# BluJoy-2_1.net
KiCad netlist of a schematic drawn in EAGLE
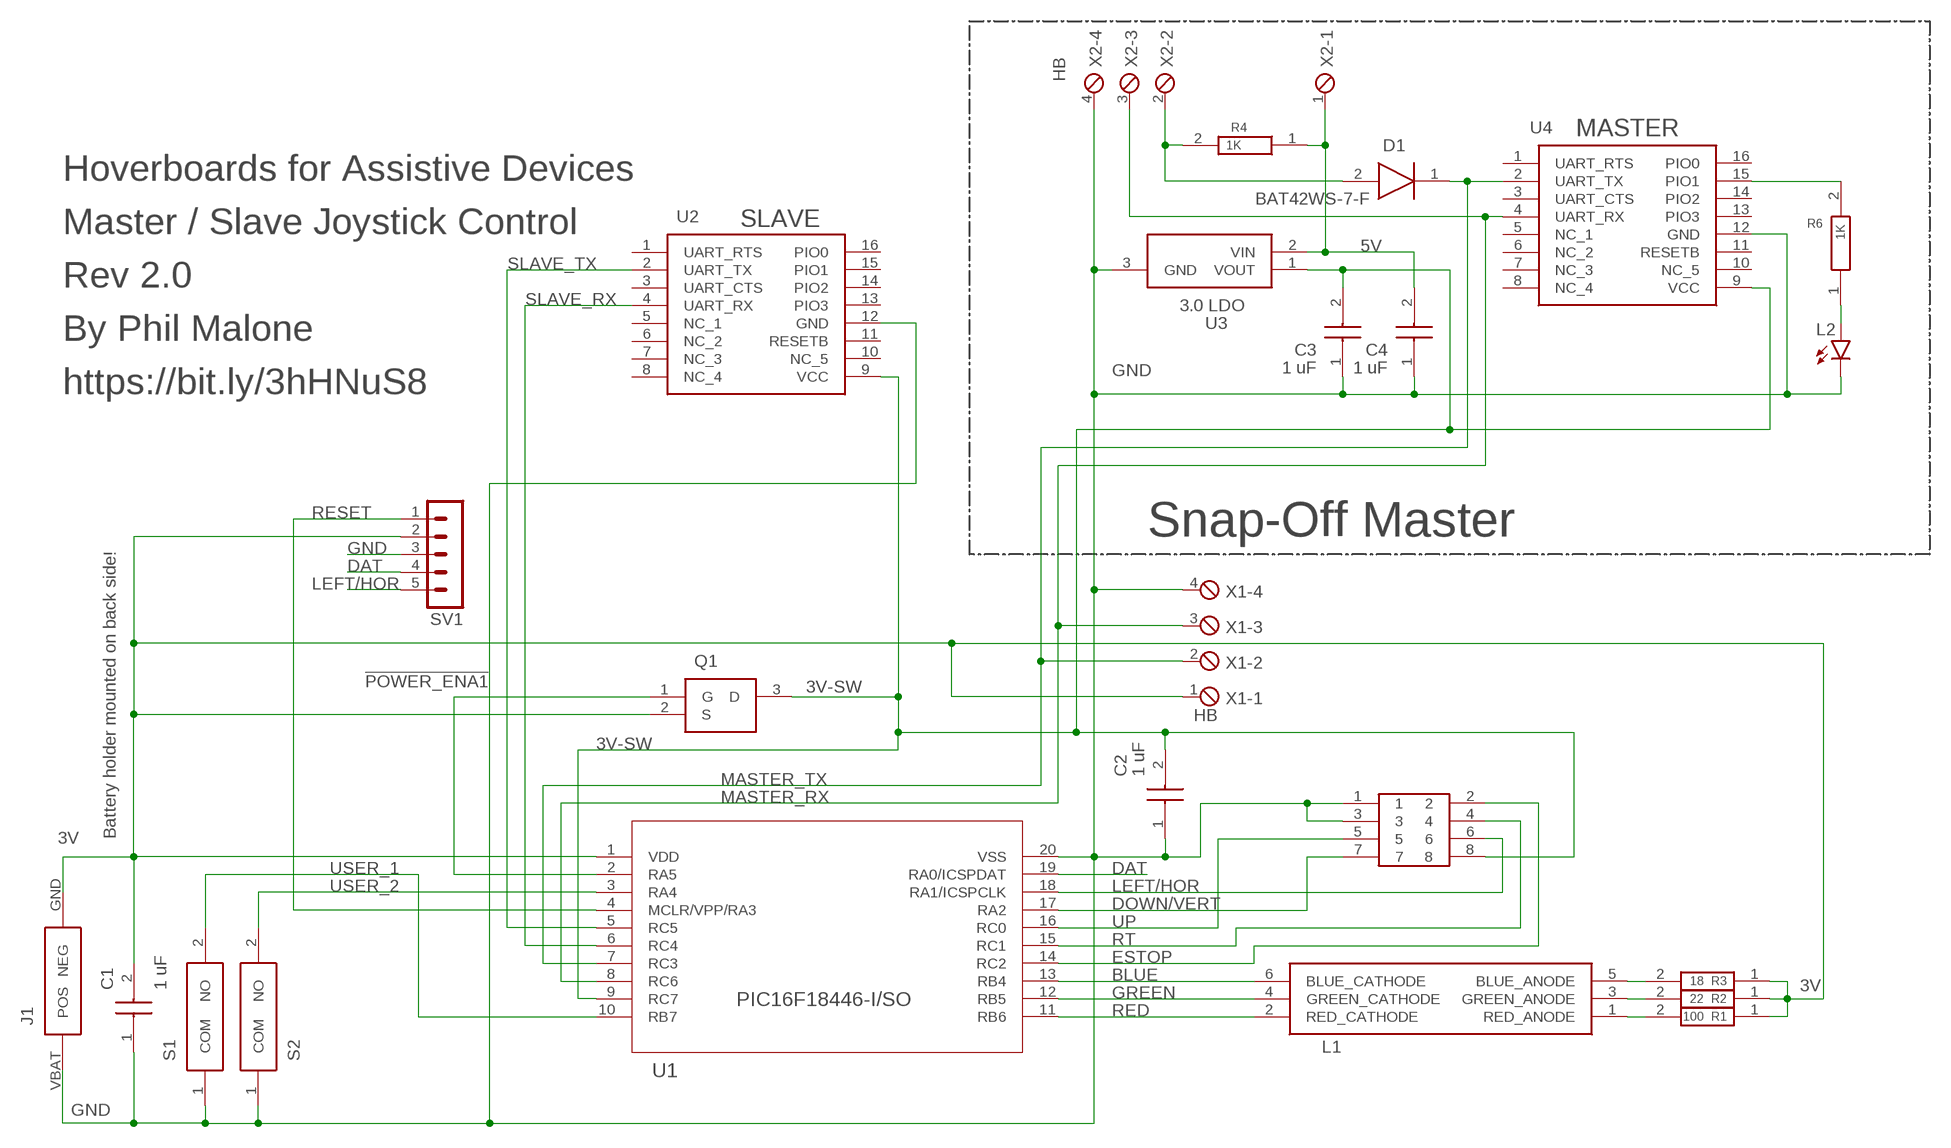
[diagram p0: schematic, sheet 1]

(export (version "E")
  (design (tool "Eeschema 10.0.6"))
  (components
    (comp (ref "C1")
      (value "1 uF")
      (footprint "eagle-import:CAPC1608X90N")
      (fields
        (field (name "MANUFACTURER_PART_NUMBER") "CC0603KRX7R7BB104")
        (field (name "MOUSER_PART_NUMBER") "603-CC603KRX7R7BB104")
        (field (name "RS_PART_NUMBER") "6698763")
      )
      (libsource (lib "eagle-import") (part "CC0603KRX7R7BB104"))
    )
    (comp (ref "C2")
      (value "1 uF")
      (footprint "eagle-import:CAPC1608X90N")
      (fields
        (field (name "MANUFACTURER_PART_NUMBER") "CC0603KRX7R7BB104")
        (field (name "MOUSER_PART_NUMBER") "603-CC603KRX7R7BB104")
        (field (name "RS_PART_NUMBER") "6698763")
      )
      (libsource (lib "eagle-import") (part "CC0603KRX7R7BB104"))
    )
    (comp (ref "C3")
      (value "1 uF")
      (footprint "eagle-import:CAPC1608X90N")
      (fields
        (field (name "MANUFACTURER_PART_NUMBER") "CC0603KRX7R7BB104")
        (field (name "MOUSER_PART_NUMBER") "603-CC603KRX7R7BB104")
        (field (name "RS_PART_NUMBER") "6698763")
      )
      (libsource (lib "eagle-import") (part "CC0603KRX7R7BB104"))
    )
    (comp (ref "C4")
      (value "1 uF")
      (footprint "eagle-import:CAPC1608X90N")
      (fields
        (field (name "MANUFACTURER_PART_NUMBER") "CC0603KRX7R7BB104")
        (field (name "MOUSER_PART_NUMBER") "603-CC603KRX7R7BB104")
        (field (name "RS_PART_NUMBER") "6698763")
      )
      (libsource (lib "eagle-import") (part "CC0603KRX7R7BB104"))
    )
    (comp (ref "D1")
      (value "BAT42WS-7-F")
      (footprint "eagle-import:SOD2513X120N")
      (fields (field (name "MOUSER_PART_NUMBER") "621-BAT42WS-F"))
      (libsource (lib "eagle-import") (part "BAT42WS-7-F"))
    )
    (comp (ref "J1")
      (value "2468")
      (footprint "eagle-import:2468")
      (fields (field (name "MOUSER_PART_NUMBER") "534-2468") (field (name "RS_PART_NUMBER") "2794965"))
      (libsource (lib "eagle-import") (part "2468"))
    )
    (comp (ref "J2")
      (value "PHOENIX3.5X8-B")
      (footprint "eagle-import:1751303")
      (libsource (lib "eagle-import") (part "PHOENIX3.5X8-B"))
    )
    (comp (ref "L1")
      (value "ASMB-TTF0-0A20B")
      (footprint "eagle-import:ASMBTTF00A20B")
      (fields (field (name "MOUSER_PART_NUMBER") "630-ASMB-TTF0-0A20B"))
      (libsource (lib "eagle-import") (part "ASMB-TTF0-0A20B"))
    )
    (comp (ref "L2")
      (value "LEDCHIP-LED0603")
      (footprint "eagle-import:CHIP-LED0603")
      (libsource (lib "eagle-import") (part "LEDCHIP-LED0603"))
    )
    (comp (ref "Q1")
      (value "P-FET")
      (footprint "eagle-import:SOT96P237X111-3N")
      (fields
        (field (name "ARROW_PART_NUMBER") "NTR4171PT1G")
        (field (name "MOUSER_PART_NUMBER") "863-NTR4171PT1G")
      )
      (libsource (lib "eagle-import") (part "NTR4171PT1G"))
    )
    (comp (ref "R1")
      (value "100")
      (footprint "eagle-import:RESC1608X50N")
      (fields
        (field (name "MANUFACTURER_PART_NUMBER") "CRCW0603240RFKEB")
        (field (name "MOUSER_PART_NUMBER") "71-CRCW0603240RFKEB")
      )
      (libsource (lib "eagle-import") (part "CRCW0603240RFKEB"))
    )
    (comp (ref "R2")
      (value "22")
      (footprint "eagle-import:RESC1608X50N")
      (fields
        (field (name "MANUFACTURER_PART_NUMBER") "CRCW0603240RFKEB")
        (field (name "MOUSER_PART_NUMBER") "71-CRCW0603240RFKEB")
      )
      (libsource (lib "eagle-import") (part "CRCW0603240RFKEB"))
    )
    (comp (ref "R3")
      (value "18")
      (footprint "eagle-import:RESC1608X50N")
      (fields
        (field (name "MANUFACTURER_PART_NUMBER") "CRCW0603240RFKEB")
        (field (name "MOUSER_PART_NUMBER") "71-CRCW0603240RFKEB")
      )
      (libsource (lib "eagle-import") (part "CRCW0603240RFKEB"))
    )
    (comp (ref "R4")
      (value "1K")
      (footprint "eagle-import:RESC1608X50N")
      (fields
        (field (name "MANUFACTURER_PART_NUMBER") "CRCW0603240RFKEB")
        (field (name "MOUSER_PART_NUMBER") "71-CRCW0603240RFKEB")
      )
      (libsource (lib "eagle-import") (part "CRCW0603240RFKEB"))
    )
    (comp (ref "R6")
      (value "1K")
      (footprint "eagle-import:RESC1608X50N")
      (fields
        (field (name "MANUFACTURER_PART_NUMBER") "CRCW0603240RFKEB")
        (field (name "MOUSER_PART_NUMBER") "71-CRCW0603240RFKEB")
      )
      (libsource (lib "eagle-import") (part "CRCW0603240RFKEB"))
    )
    (comp (ref "S1")
      (value "PTS636_SK25J_SMTR_LFS")
      (footprint "eagle-import:PTS636SK25JSMTRLFS")
      (fields
        (field (name "MANUFACTURER_PART_NUMBER") "PTS636 SK25J SMTR LFS")
        (field (name "MOUSER_PART_NUMBER") "611-PTS636SK25JSMTRL")
      )
      (libsource (lib "eagle-import") (part "PTS636_SK25J_SMTR_LFS"))
    )
    (comp (ref "S2")
      (value "PTS636_SK25J_SMTR_LFS")
      (footprint "eagle-import:PTS636SK25JSMTRLFS")
      (fields
        (field (name "MANUFACTURER_PART_NUMBER") "PTS636 SK25J SMTR LFS")
        (field (name "MOUSER_PART_NUMBER") "611-PTS636SK25JSMTRL")
      )
      (libsource (lib "eagle-import") (part "PTS636_SK25J_SMTR_LFS"))
    )
    (comp (ref "SV1")
      (value "PICKIT")
      (footprint "eagle-import:MA05-1")
      (libsource (lib "eagle-import") (part "PICKIT"))
    )
    (comp (ref "U1")
      (value "PIC16F18446-I/SO")
      (footprint "eagle-import:SOIC20_SO_MCH")
      (fields
        (field (name "MANUFACTURER_PART_NUMBER") "PIC16F15345-I/SO")
        (field (name "COPYRIGHT") "Copyright (C) 2018 Accelerated Designs. All rights reserved")
      )
      (libsource (lib "eagle-import") (part "PIC16F15345-I/SO"))
    )
    (comp (ref "U2")
      (value "HM-11")
      (footprint "eagle-import:HM-11-MODULE")
      (libsource (lib "eagle-import") (part "HM-11"))
    )
    (comp (ref "U3")
      (value "3.0 LDO")
      (footprint "eagle-import:SOT95P237X112-3N")
      (fields
        (field (name "ARROW_PART_NUMBER") "MCP1812AT-030/TT")
        (field (name "MOUSER_PART_NUMBER") "579-MCP1812AT-030/TT")
      )
      (libsource (lib "eagle-import") (part "MCP1812AT-030_TT"))
    )
    (comp (ref "U4")
      (value "HM-11")
      (footprint "eagle-import:HM-11-MODULE")
      (libsource (lib "eagle-import") (part "HM-11"))
    )
    (comp (ref "X1")
      (value "HB")
      (footprint "eagle-import:4POL254")
      (libsource (lib "eagle-import") (part "MPT4"))
    )
    (comp (ref "X2")
      (value "HB")
      (footprint "eagle-import:4POL254")
      (libsource (lib "eagle-import") (part "MPT4"))
    )
  )
  (nets
    (net (code "1") (name "/3V") (class "Default")
      (node (ref "C1") (pin "2") (pinfunction "C2_2") (pintype "bidirectional"))
      (node (ref "J1") (pin "GND") (pinfunction "NEG_GND") (pintype "bidirectional"))
      (node (ref "Q1") (pin "2") (pinfunction "S_2") (pintype "bidirectional"))
      (node (ref "R1") (pin "1") (pinfunction "1_1") (pintype "bidirectional"))
      (node (ref "R2") (pin "1") (pinfunction "1_1") (pintype "bidirectional"))
      (node (ref "R3") (pin "1") (pinfunction "1_1") (pintype "bidirectional"))
      (node (ref "SV1") (pin "2") (pinfunction "2_2") (pintype "passive"))
      (node (ref "U1") (pin "1") (pinfunction "VDD_1") (pintype "power_in"))
      (node (ref "X1") (pin "1") (pinfunction "1_1") (pintype "passive"))
    )
    (net (code "2") (name "/3V-SW") (class "Default")
      (node (ref "C2") (pin "2") (pinfunction "C2_2") (pintype "bidirectional"))
      (node (ref "C3") (pin "2") (pinfunction "C2_2") (pintype "bidirectional"))
      (node (ref "J2") (pin "8") (pinfunction "8_8") (pintype "bidirectional"))
      (node (ref "Q1") (pin "3") (pinfunction "D_3") (pintype "bidirectional"))
      (node (ref "U1") (pin "9") (pinfunction "RC7_9") (pintype "bidirectional"))
      (node (ref "U2") (pin "9") (pinfunction "VCC_9") (pintype "power_in"))
      (node (ref "U3") (pin "1") (pinfunction "VOUT_1") (pintype "power_in"))
      (node (ref "U4") (pin "9") (pinfunction "VCC_9") (pintype "power_in"))
    )
    (net (code "3") (name "/5V") (class "Default")
      (node (ref "C4") (pin "2") (pinfunction "C2_2") (pintype "bidirectional"))
      (node (ref "R4") (pin "1") (pinfunction "1_1") (pintype "bidirectional"))
      (node (ref "U3") (pin "2") (pinfunction "VIN_2") (pintype "power_in"))
      (node (ref "X2") (pin "1") (pinfunction "1_1") (pintype "passive"))
    )
    (net (code "4") (name "/BLUE") (class "Default")
      (node (ref "L1") (pin "6") (pinfunction "BLUE_CATHODE_6") (pintype "bidirectional"))
      (node (ref "U1") (pin "13") (pinfunction "RB4_13") (pintype "bidirectional"))
    )
    (net (code "5") (name "/DAT") (class "Default")
      (node (ref "SV1") (pin "4") (pinfunction "4_4") (pintype "passive"))
      (node (ref "U1") (pin "19") (pinfunction "RA0/ICSPDAT_19") (pintype "bidirectional"))
    )
    (net (code "6") (name "/DOWN{slash}VERT") (class "Default")
      (node (ref "J2") (pin "7") (pinfunction "7_7") (pintype "bidirectional"))
      (node (ref "U1") (pin "17") (pinfunction "RA2_17") (pintype "bidirectional"))
    )
    (net (code "7") (name "/ESTOP") (class "Default")
      (node (ref "J2") (pin "2") (pinfunction "2_2") (pintype "bidirectional"))
      (node (ref "U1") (pin "14") (pinfunction "RC2_14") (pintype "bidirectional"))
    )
    (net (code "8") (name "/GND") (class "Default")
      (node (ref "C1") (pin "1") (pinfunction "C1_1") (pintype "bidirectional"))
      (node (ref "C2") (pin "1") (pinfunction "C1_1") (pintype "bidirectional"))
      (node (ref "C3") (pin "1") (pinfunction "C1_1") (pintype "bidirectional"))
      (node (ref "C4") (pin "1") (pinfunction "C1_1") (pintype "bidirectional"))
      (node (ref "J1") (pin "VBAT") (pinfunction "POS_VBAT") (pintype "bidirectional"))
      (node (ref "J2") (pin "1") (pinfunction "1_1") (pintype "bidirectional"))
      (node (ref "J2") (pin "3") (pinfunction "3_3") (pintype "bidirectional"))
      (node (ref "L2") (pin "C") (pinfunction "C_C") (pintype "passive"))
      (node (ref "S1") (pin "1") (pinfunction "COM_1") (pintype "bidirectional"))
      (node (ref "S2") (pin "1") (pinfunction "COM_1") (pintype "bidirectional"))
      (node (ref "SV1") (pin "3") (pinfunction "3_3") (pintype "passive"))
      (node (ref "U1") (pin "20") (pinfunction "VSS_20") (pintype "passive"))
      (node (ref "U2") (pin "12") (pinfunction "GND_12") (pintype "power_in"))
      (node (ref "U3") (pin "3") (pinfunction "GND_3") (pintype "power_in"))
      (node (ref "U4") (pin "12") (pinfunction "GND_12") (pintype "power_in"))
      (node (ref "X1") (pin "4") (pinfunction "1_4") (pintype "passive"))
      (node (ref "X2") (pin "4") (pinfunction "1_4") (pintype "passive"))
    )
    (net (code "9") (name "/GREEN") (class "Default")
      (node (ref "L1") (pin "4") (pinfunction "GREEN_CATHODE_4") (pintype "bidirectional"))
      (node (ref "U1") (pin "12") (pinfunction "RB5_12") (pintype "bidirectional"))
    )
    (net (code "10") (name "/LEFT{slash}HOR") (class "Default")
      (node (ref "J2") (pin "6") (pinfunction "6_6") (pintype "bidirectional"))
      (node (ref "SV1") (pin "5") (pinfunction "5_5") (pintype "passive"))
      (node (ref "U1") (pin "18") (pinfunction "RA1/ICSPCLK_18") (pintype "bidirectional"))
    )
    (net (code "11") (name "/MASTER_RX") (class "Default")
      (node (ref "U1") (pin "8") (pinfunction "RC6_8") (pintype "bidirectional"))
      (node (ref "U4") (pin "4") (pinfunction "UART_RX_4") (pintype "bidirectional"))
      (node (ref "X1") (pin "3") (pinfunction "1_3") (pintype "passive"))
      (node (ref "X2") (pin "3") (pinfunction "1_3") (pintype "passive"))
    )
    (net (code "12") (name "/MASTER_TX") (class "Default")
      (node (ref "D1") (pin "1") (pinfunction "K_1") (pintype "bidirectional"))
      (node (ref "U1") (pin "7") (pinfunction "RC3_7") (pintype "bidirectional"))
      (node (ref "U4") (pin "2") (pinfunction "UART_TX_2") (pintype "bidirectional"))
      (node (ref "X1") (pin "2") (pinfunction "1_2") (pintype "passive"))
    )
    (net (code "13") (name "/RED") (class "Default")
      (node (ref "L1") (pin "2") (pinfunction "RED_CATHODE_2") (pintype "bidirectional"))
      (node (ref "U1") (pin "11") (pinfunction "RB6_11") (pintype "bidirectional"))
    )
    (net (code "14") (name "/RESET") (class "Default")
      (node (ref "SV1") (pin "1") (pinfunction "1_1") (pintype "passive"))
      (node (ref "U1") (pin "4") (pinfunction "MCLR/VPP/RA3_4") (pintype "power_in"))
    )
    (net (code "15") (name "/RT") (class "Default")
      (node (ref "J2") (pin "4") (pinfunction "4_4") (pintype "bidirectional"))
      (node (ref "U1") (pin "15") (pinfunction "RC1_15") (pintype "bidirectional"))
    )
    (net (code "16") (name "/SLAVE_RX") (class "Default")
      (node (ref "U1") (pin "6") (pinfunction "RC4_6") (pintype "bidirectional"))
      (node (ref "U2") (pin "4") (pinfunction "UART_RX_4") (pintype "bidirectional"))
    )
    (net (code "17") (name "/SLAVE_TX") (class "Default")
      (node (ref "U1") (pin "5") (pinfunction "RC5_5") (pintype "bidirectional"))
      (node (ref "U2") (pin "2") (pinfunction "UART_TX_2") (pintype "bidirectional"))
    )
    (net (code "18") (name "/UP") (class "Default")
      (node (ref "J2") (pin "5") (pinfunction "5_5") (pintype "bidirectional"))
      (node (ref "U1") (pin "16") (pinfunction "RC0_16") (pintype "bidirectional"))
    )
    (net (code "19") (name "/USER_1") (class "Default")
      (node (ref "S1") (pin "2") (pinfunction "NO_2") (pintype "bidirectional"))
      (node (ref "U1") (pin "10") (pinfunction "RB7_10") (pintype "bidirectional"))
    )
    (net (code "20") (name "/USER_2") (class "Default")
      (node (ref "S2") (pin "2") (pinfunction "NO_2") (pintype "bidirectional"))
      (node (ref "U1") (pin "3") (pinfunction "RA4_3") (pintype "bidirectional"))
    )
    (net (code "21") (name "/~{POWER_ENA1}") (class "Default")
      (node (ref "Q1") (pin "1") (pinfunction "G_1") (pintype "bidirectional"))
      (node (ref "U1") (pin "2") (pinfunction "RA5_2") (pintype "bidirectional"))
    )
    (net (code "22") (name "Net-(D1-A)") (class "Default")
      (node (ref "D1") (pin "2") (pinfunction "A_2") (pintype "bidirectional"))
      (node (ref "R4") (pin "2") (pinfunction "2_2") (pintype "bidirectional"))
      (node (ref "X2") (pin "2") (pinfunction "1_2") (pintype "passive"))
    )
    (net (code "23") (name "Net-(L1-BLUE_ANODE)") (class "Default")
      (node (ref "L1") (pin "5") (pinfunction "BLUE_ANODE_5") (pintype "bidirectional"))
      (node (ref "R3") (pin "2") (pinfunction "2_2") (pintype "bidirectional"))
    )
    (net (code "24") (name "Net-(L1-GREEN_ANODE)") (class "Default")
      (node (ref "L1") (pin "3") (pinfunction "GREEN_ANODE_3") (pintype "bidirectional"))
      (node (ref "R2") (pin "2") (pinfunction "2_2") (pintype "bidirectional"))
    )
    (net (code "25") (name "Net-(L1-RED_ANODE)") (class "Default")
      (node (ref "L1") (pin "1") (pinfunction "RED_ANODE_1") (pintype "bidirectional"))
      (node (ref "R1") (pin "2") (pinfunction "2_2") (pintype "bidirectional"))
    )
    (net (code "26") (name "Net-(L2-PadA)") (class "Default")
      (node (ref "L2") (pin "A") (pinfunction "A_A") (pintype "passive"))
      (node (ref "R6") (pin "1") (pinfunction "1_1") (pintype "bidirectional"))
    )
    (net (code "27") (name "Net-(U4-PIO1)") (class "Default")
      (node (ref "R6") (pin "2") (pinfunction "2_2") (pintype "bidirectional"))
      (node (ref "U4") (pin "15") (pinfunction "PIO1_15") (pintype "bidirectional"))
    )
    (net (code "28") (name "unconnected-(U2-NC_1-Pad5)") (class "Default")
      (node (ref "U2") (pin "5") (pinfunction "NC_1_5") (pintype "bidirectional"))
    )
    (net (code "29") (name "unconnected-(U2-NC_2-Pad6)") (class "Default")
      (node (ref "U2") (pin "6") (pinfunction "NC_2_6") (pintype "bidirectional"))
    )
    (net (code "30") (name "unconnected-(U2-NC_3-Pad7)") (class "Default")
      (node (ref "U2") (pin "7") (pinfunction "NC_3_7") (pintype "bidirectional"))
    )
    (net (code "31") (name "unconnected-(U2-NC_4-Pad8)") (class "Default")
      (node (ref "U2") (pin "8") (pinfunction "NC_4_8") (pintype "bidirectional"))
    )
    (net (code "32") (name "unconnected-(U2-NC_5-Pad10)") (class "Default")
      (node (ref "U2") (pin "10") (pinfunction "NC_5_10") (pintype "bidirectional"))
    )
    (net (code "33") (name "unconnected-(U2-PIO0-Pad16)") (class "Default")
      (node (ref "U2") (pin "16") (pinfunction "PIO0_16") (pintype "bidirectional"))
    )
    (net (code "34") (name "unconnected-(U2-PIO1-Pad15)") (class "Default")
      (node (ref "U2") (pin "15") (pinfunction "PIO1_15") (pintype "bidirectional"))
    )
    (net (code "35") (name "unconnected-(U2-PIO2-Pad14)") (class "Default")
      (node (ref "U2") (pin "14") (pinfunction "PIO2_14") (pintype "bidirectional"))
    )
    (net (code "36") (name "unconnected-(U2-PIO3-Pad13)") (class "Default")
      (node (ref "U2") (pin "13") (pinfunction "PIO3_13") (pintype "bidirectional"))
    )
    (net (code "37") (name "unconnected-(U2-RESETB-Pad11)") (class "Default")
      (node (ref "U2") (pin "11") (pinfunction "RESETB_11") (pintype "bidirectional"))
    )
    (net (code "38") (name "unconnected-(U2-UART_CTS-Pad3)") (class "Default")
      (node (ref "U2") (pin "3") (pinfunction "UART_CTS_3") (pintype "bidirectional"))
    )
    (net (code "39") (name "unconnected-(U2-UART_RTS-Pad1)") (class "Default")
      (node (ref "U2") (pin "1") (pinfunction "UART_RTS_1") (pintype "bidirectional"))
    )
    (net (code "40") (name "unconnected-(U4-NC_1-Pad5)") (class "Default")
      (node (ref "U4") (pin "5") (pinfunction "NC_1_5") (pintype "bidirectional"))
    )
    (net (code "41") (name "unconnected-(U4-NC_2-Pad6)") (class "Default")
      (node (ref "U4") (pin "6") (pinfunction "NC_2_6") (pintype "bidirectional"))
    )
    (net (code "42") (name "unconnected-(U4-NC_3-Pad7)") (class "Default")
      (node (ref "U4") (pin "7") (pinfunction "NC_3_7") (pintype "bidirectional"))
    )
    (net (code "43") (name "unconnected-(U4-NC_4-Pad8)") (class "Default")
      (node (ref "U4") (pin "8") (pinfunction "NC_4_8") (pintype "bidirectional"))
    )
    (net (code "44") (name "unconnected-(U4-NC_5-Pad10)") (class "Default")
      (node (ref "U4") (pin "10") (pinfunction "NC_5_10") (pintype "bidirectional"))
    )
    (net (code "45") (name "unconnected-(U4-PIO0-Pad16)") (class "Default")
      (node (ref "U4") (pin "16") (pinfunction "PIO0_16") (pintype "bidirectional"))
    )
    (net (code "46") (name "unconnected-(U4-PIO2-Pad14)") (class "Default")
      (node (ref "U4") (pin "14") (pinfunction "PIO2_14") (pintype "bidirectional"))
    )
    (net (code "47") (name "unconnected-(U4-PIO3-Pad13)") (class "Default")
      (node (ref "U4") (pin "13") (pinfunction "PIO3_13") (pintype "bidirectional"))
    )
    (net (code "48") (name "unconnected-(U4-RESETB-Pad11)") (class "Default")
      (node (ref "U4") (pin "11") (pinfunction "RESETB_11") (pintype "bidirectional"))
    )
    (net (code "49") (name "unconnected-(U4-UART_CTS-Pad3)") (class "Default")
      (node (ref "U4") (pin "3") (pinfunction "UART_CTS_3") (pintype "bidirectional"))
    )
    (net (code "50") (name "unconnected-(U4-UART_RTS-Pad1)") (class "Default")
      (node (ref "U4") (pin "1") (pinfunction "UART_RTS_1") (pintype "bidirectional"))
    )
  )
)
